# TTP223.net
KiCad netlist of a schematic drawn in Altium Designer
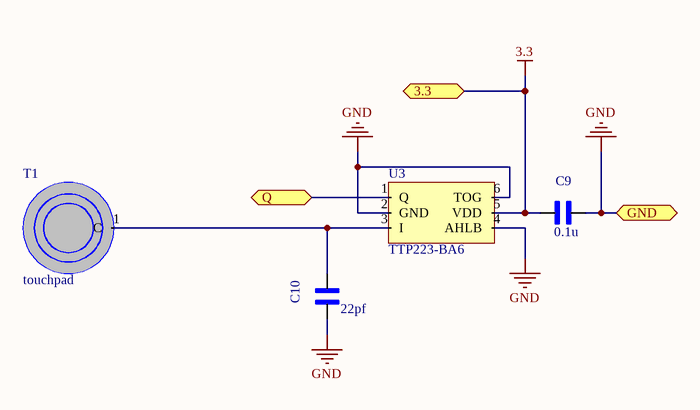
[diagram p0: TTP223.SchDoc]

(export (version "E")
  (design (tool "Eeschema 10.0.6"))
  (components
    (comp (ref "C9")
      (value "0.1u")
      (footprint "*CAPC1608X90")
      (description "Cap Thin Film 0.1uf 50v 0603")
      (fields (field (name "MF") "AVX") (field (name "MP") "GX035C104MAT2-500 or CL10B104JB8NNNC"))
      (libsource (lib "lib") (part "GX035C104MAT2-500"))
    )
    (comp (ref "C10")
      (value "22pf")
      (footprint "*CAPC1608X90")
      (description "Cap Thin Film 0.1uf 50v 0603")
      (fields (field (name "MF") "AVX") (field (name "MP") "GX035C104MAT2-500 or CL10B104JB8NNNC"))
      (libsource (lib "lib") (part "GX035C104MAT2-500"))
    )
    (comp (ref "T1") (value "touchpad") (footprint "TANKSENSOR") (libsource (lib "lib") (part "touchpad")))
    (comp (ref "U3") (value "TTP223-BA6") (footprint "SOT23-6") (libsource (lib "lib") (part "TTP223-BA6")))
  )
  (nets
    (net (code "1") (name "/Q") (class "Default")
      (node (ref "U3") (pin "1") (pinfunction "Q_1") (pintype "passive"))
    )
    (net (code "2") (name "3.3") (class "Default")
      (node (ref "C9") (pin "2") (pinfunction "2_2") (pintype "passive"))
      (node (ref "U3") (pin "5") (pinfunction "VDD_5") (pintype "passive"))
    )
    (net (code "3") (name "GND") (class "Default")
      (node (ref "C10") (pin "2") (pinfunction "2_2") (pintype "passive"))
      (node (ref "C9") (pin "1") (pinfunction "1_1") (pintype "passive"))
      (node (ref "U3") (pin "2") (pinfunction "GND_2") (pintype "passive"))
      (node (ref "U3") (pin "4") (pinfunction "AHLB_4") (pintype "passive"))
      (node (ref "U3") (pin "6") (pinfunction "TOG_6") (pintype "passive"))
    )
    (net (code "4") (name "Net-(T1-C)") (class "Default")
      (node (ref "C10") (pin "1") (pinfunction "1_1") (pintype "passive"))
      (node (ref "T1") (pin "1") (pinfunction "C_1") (pintype "passive"))
      (node (ref "U3") (pin "3") (pinfunction "I_3") (pintype "passive"))
    )
  )
)
